# 1a.net
KiCad netlist of a schematic drawn in EAGLE
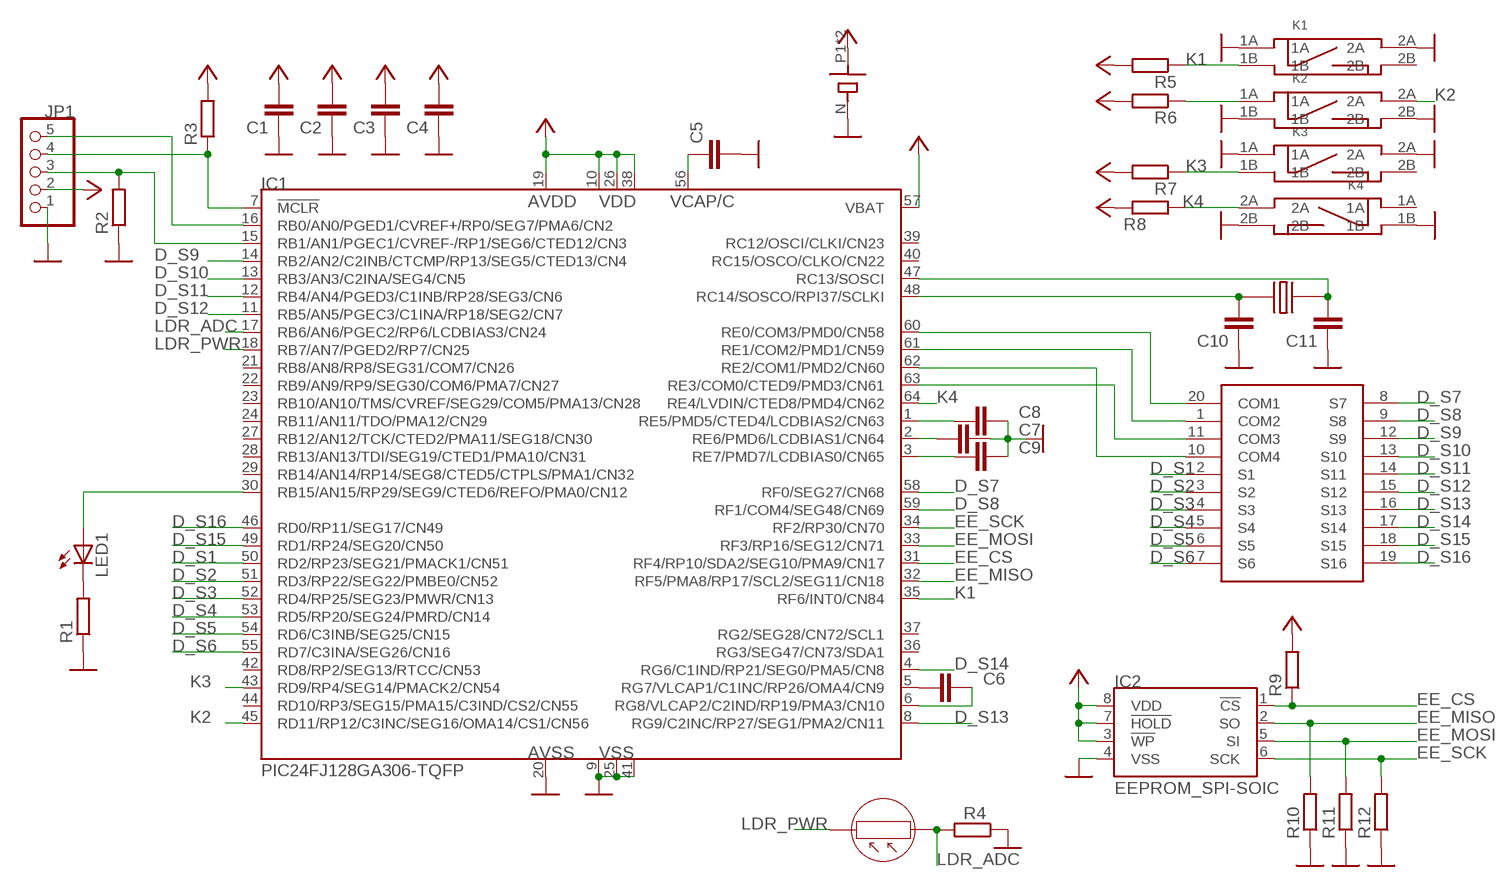
[diagram p0: schematic, sheet 1]

(export (version "E")
  (design (tool "Eeschema 10.0.6"))
  (components
    (comp (ref "C1")
      (value "C_1206")
      (footprint "eagle-import:R1206")
      (libsource (lib "eagle-import") (part "C_1206"))
    )
    (comp (ref "C2")
      (value "C_0603")
      (footprint "eagle-import:0603")
      (libsource (lib "eagle-import") (part "C_0603"))
    )
    (comp (ref "C3")
      (value "C_0603")
      (footprint "eagle-import:0603")
      (libsource (lib "eagle-import") (part "C_0603"))
    )
    (comp (ref "C4")
      (value "C_0603")
      (footprint "eagle-import:0603")
      (libsource (lib "eagle-import") (part "C_0603"))
    )
    (comp (ref "C5")
      (value "C_0603")
      (footprint "eagle-import:0603")
      (libsource (lib "eagle-import") (part "C_0603"))
    )
    (comp (ref "C6")
      (value "C_0603")
      (footprint "eagle-import:0603")
      (libsource (lib "eagle-import") (part "C_0603"))
    )
    (comp (ref "C7")
      (value "C_0603")
      (footprint "eagle-import:0603")
      (libsource (lib "eagle-import") (part "C_0603"))
    )
    (comp (ref "C8")
      (value "C_0603")
      (footprint "eagle-import:0603")
      (libsource (lib "eagle-import") (part "C_0603"))
    )
    (comp (ref "C9")
      (value "C_0603")
      (footprint "eagle-import:0603")
      (libsource (lib "eagle-import") (part "C_0603"))
    )
    (comp (ref "C10")
      (value "C_0603")
      (footprint "eagle-import:0603")
      (libsource (lib "eagle-import") (part "C_0603"))
    )
    (comp (ref "C11")
      (value "C_0603")
      (footprint "eagle-import:0603")
      (libsource (lib "eagle-import") (part "C_0603"))
    )
    (comp (ref "IC1")
      (value "PIC24FJ128GA306-TQFP")
      (footprint "eagle-import:TQFP64-10X10")
      (libsource (lib "eagle-import") (part "PIC24FJ128GA306-TQFP"))
    )
    (comp (ref "IC2")
      (value "EEPROM_SPI-SOIC")
      (footprint "eagle-import:SO-08")
      (libsource (lib "eagle-import") (part "EEPROM_SPI-SOIC"))
    )
    (comp (ref "JP1")
      (value "PINHD-1X05_2.00")
      (footprint "eagle-import:1X05M")
      (libsource (lib "eagle-import") (part "PINHD-1X05_2.00"))
    )
    (comp (ref "K1")
      (value "SWITCH_BD_B")
      (footprint "eagle-import:SW_SMD2")
      (libsource (lib "eagle-import") (part "SWITCH_BD_B"))
    )
    (comp (ref "K2")
      (value "SWITCH_BD_B")
      (footprint "eagle-import:SW_SMD2")
      (libsource (lib "eagle-import") (part "SWITCH_BD_B"))
    )
    (comp (ref "K3")
      (value "SWITCH_BD_B")
      (footprint "eagle-import:SW_SMD2")
      (libsource (lib "eagle-import") (part "SWITCH_BD_B"))
    )
    (comp (ref "K4")
      (value "SWITCH_BD_B")
      (footprint "eagle-import:SW_SMD2")
      (libsource (lib "eagle-import") (part "SWITCH_BD_B"))
    )
    (comp (ref "LCD1")
      (value "LCD_DE188")
      (footprint "eagle-import:LCD_DE188")
      (libsource (lib "eagle-import") (part "LCD_DE188"))
    )
    (comp (ref "LDR1")
      (value "LDR")
      (footprint "eagle-import:LDR_5")
      (libsource (lib "eagle-import") (part "LDR"))
    )
    (comp (ref "LED1")
      (value "LEDCHIPLED_0805")
      (footprint "eagle-import:CHIPLED_0805")
      (libsource (lib "eagle-import") (part "LEDCHIPLED_0805"))
    )
    (comp (ref "R1")
      (value "R_0603")
      (footprint "eagle-import:0603")
      (libsource (lib "eagle-import") (part "R_0603"))
    )
    (comp (ref "R2")
      (value "R_0603")
      (footprint "eagle-import:0603")
      (libsource (lib "eagle-import") (part "R_0603"))
    )
    (comp (ref "R3")
      (value "R_0603")
      (footprint "eagle-import:0603")
      (libsource (lib "eagle-import") (part "R_0603"))
    )
    (comp (ref "R4")
      (value "R_0603")
      (footprint "eagle-import:0603")
      (libsource (lib "eagle-import") (part "R_0603"))
    )
    (comp (ref "R5")
      (value "R_0603")
      (footprint "eagle-import:0603")
      (libsource (lib "eagle-import") (part "R_0603"))
    )
    (comp (ref "R6")
      (value "R_0603")
      (footprint "eagle-import:0603")
      (libsource (lib "eagle-import") (part "R_0603"))
    )
    (comp (ref "R7")
      (value "R_0603")
      (footprint "eagle-import:0603")
      (libsource (lib "eagle-import") (part "R_0603"))
    )
    (comp (ref "R8")
      (value "R_0603")
      (footprint "eagle-import:0603")
      (libsource (lib "eagle-import") (part "R_0603"))
    )
    (comp (ref "R9")
      (value "R_0603")
      (footprint "eagle-import:0603")
      (libsource (lib "eagle-import") (part "R_0603"))
    )
    (comp (ref "R10")
      (value "R_0603")
      (footprint "eagle-import:0603")
      (libsource (lib "eagle-import") (part "R_0603"))
    )
    (comp (ref "R11")
      (value "R_0603")
      (footprint "eagle-import:0603")
      (libsource (lib "eagle-import") (part "R_0603"))
    )
    (comp (ref "R12")
      (value "R_0603")
      (footprint "eagle-import:0603")
      (libsource (lib "eagle-import") (part "R_0603"))
    )
    (comp (ref "U$1")
      (value "BATTK3002")
      (footprint "eagle-import:BATT_KEYS3002")
      (libsource (lib "eagle-import") (part "BATTK3002"))
    )
    (comp (ref "X1")
      (value "CRYST_TC26MC146")
      (footprint "eagle-import:CRYST_MC146")
      (libsource (lib "eagle-import") (part "CRYST_TC26MC146"))
    )
  )
  (nets
    (net (code "1") (name "/D_S1") (class "Default")
      (node (ref "IC1") (pin "50") (pinfunction "RD2/RP23/SEG21/PMACK1/CN51_50") (pintype "bidirectional"))
      (node (ref "LCD1") (pin "2") (pinfunction "S1_2") (pintype "bidirectional"))
    )
    (net (code "2") (name "/D_S2") (class "Default")
      (node (ref "IC1") (pin "51") (pinfunction "RD3/RP22/SEG22/PMBE0/CN52_51") (pintype "bidirectional"))
      (node (ref "LCD1") (pin "3") (pinfunction "S2_3") (pintype "bidirectional"))
    )
    (net (code "3") (name "/D_S3") (class "Default")
      (node (ref "IC1") (pin "52") (pinfunction "RD4/RP25/SEG23/PMWR/CN13_52") (pintype "bidirectional"))
      (node (ref "LCD1") (pin "4") (pinfunction "S3_4") (pintype "bidirectional"))
    )
    (net (code "4") (name "/D_S4") (class "Default")
      (node (ref "IC1") (pin "53") (pinfunction "RD5/RP20/SEG24/PMRD/CN14_53") (pintype "bidirectional"))
      (node (ref "LCD1") (pin "5") (pinfunction "S4_5") (pintype "bidirectional"))
    )
    (net (code "5") (name "/D_S5") (class "Default")
      (node (ref "IC1") (pin "54") (pinfunction "RD6/C3INB/SEG25/CN15_54") (pintype "bidirectional"))
      (node (ref "LCD1") (pin "6") (pinfunction "S5_6") (pintype "bidirectional"))
    )
    (net (code "6") (name "/D_S6") (class "Default")
      (node (ref "IC1") (pin "55") (pinfunction "RD7/C3INA/SEG26/CN16_55") (pintype "bidirectional"))
      (node (ref "LCD1") (pin "7") (pinfunction "S6_7") (pintype "bidirectional"))
    )
    (net (code "7") (name "/D_S7") (class "Default")
      (node (ref "IC1") (pin "58") (pinfunction "RF0/SEG27/CN68_58") (pintype "bidirectional"))
      (node (ref "LCD1") (pin "8") (pinfunction "S7_8") (pintype "bidirectional"))
    )
    (net (code "8") (name "/D_S8") (class "Default")
      (node (ref "IC1") (pin "59") (pinfunction "RF1/COM4/SEG48/CN69_59") (pintype "bidirectional"))
      (node (ref "LCD1") (pin "9") (pinfunction "S8_9") (pintype "bidirectional"))
    )
    (net (code "9") (name "/D_S9") (class "Default")
      (node (ref "IC1") (pin "14") (pinfunction "RB2/AN2/C2INB/CTCMP/RP13/SEG5/CTED13/CN4_14") (pintype "bidirectional"))
      (node (ref "LCD1") (pin "12") (pinfunction "S9_12") (pintype "bidirectional"))
    )
    (net (code "10") (name "/D_S10") (class "Default")
      (node (ref "IC1") (pin "13") (pinfunction "RB3/AN3/C2INA/SEG4/CN5_13") (pintype "bidirectional"))
      (node (ref "LCD1") (pin "13") (pinfunction "S10_13") (pintype "bidirectional"))
    )
    (net (code "11") (name "/D_S11") (class "Default")
      (node (ref "IC1") (pin "12") (pinfunction "RB4/AN4/PGED3/C1INB/RP28/SEG3/CN6_12") (pintype "bidirectional"))
      (node (ref "LCD1") (pin "14") (pinfunction "S11_14") (pintype "bidirectional"))
    )
    (net (code "12") (name "/D_S12") (class "Default")
      (node (ref "IC1") (pin "11") (pinfunction "RB5/AN5/PGEC3/C1INA/RP18/SEG2/CN7_11") (pintype "bidirectional"))
      (node (ref "LCD1") (pin "15") (pinfunction "S12_15") (pintype "bidirectional"))
    )
    (net (code "13") (name "/D_S13") (class "Default")
      (node (ref "IC1") (pin "8") (pinfunction "RG9/C2INC/RP27/SEG1/PMA2/CN11_8") (pintype "bidirectional"))
      (node (ref "LCD1") (pin "16") (pinfunction "S13_16") (pintype "bidirectional"))
    )
    (net (code "14") (name "/D_S14") (class "Default")
      (node (ref "IC1") (pin "4") (pinfunction "RG6/C1IND/RP21/SEG0/PMA5/CN8_4") (pintype "bidirectional"))
      (node (ref "LCD1") (pin "17") (pinfunction "S14_17") (pintype "bidirectional"))
    )
    (net (code "15") (name "/D_S15") (class "Default")
      (node (ref "IC1") (pin "49") (pinfunction "RD1/RP24/SEG20/CN50_49") (pintype "bidirectional"))
      (node (ref "LCD1") (pin "18") (pinfunction "S15_18") (pintype "bidirectional"))
    )
    (net (code "16") (name "/D_S16") (class "Default")
      (node (ref "IC1") (pin "46") (pinfunction "RD0/RP11/SEG17/CN49_46") (pintype "bidirectional"))
      (node (ref "LCD1") (pin "19") (pinfunction "S16_19") (pintype "bidirectional"))
    )
    (net (code "17") (name "/EE_CS") (class "Default")
      (node (ref "IC1") (pin "31") (pinfunction "RF4/RP10/SDA2/SEG10/PMA9/CN17_31") (pintype "bidirectional"))
      (node (ref "IC2") (pin "1") (pinfunction "~{CS}_1") (pintype "input"))
      (node (ref "R9") (pin "1") (pinfunction "1_1") (pintype "passive"))
    )
    (net (code "18") (name "/EE_MISO") (class "Default")
      (node (ref "IC1") (pin "32") (pinfunction "RF5/PMA8/RP17/SCL2/SEG11/CN18_32") (pintype "bidirectional"))
      (node (ref "IC2") (pin "2") (pinfunction "SO_2") (pintype "input"))
      (node (ref "R10") (pin "2") (pinfunction "2_2") (pintype "passive"))
    )
    (net (code "19") (name "/EE_MOSI") (class "Default")
      (node (ref "IC1") (pin "33") (pinfunction "RF3/RP16/SEG12/CN71_33") (pintype "bidirectional"))
      (node (ref "IC2") (pin "5") (pinfunction "SI_5") (pintype "input"))
      (node (ref "R11") (pin "2") (pinfunction "2_2") (pintype "passive"))
    )
    (net (code "20") (name "/EE_SCK") (class "Default")
      (node (ref "IC1") (pin "34") (pinfunction "RF2/RP30/CN70_34") (pintype "bidirectional"))
      (node (ref "IC2") (pin "6") (pinfunction "SCK_6") (pintype "input"))
      (node (ref "R12") (pin "2") (pinfunction "2_2") (pintype "passive"))
    )
    (net (code "21") (name "/K1") (class "Default")
      (node (ref "IC1") (pin "35") (pinfunction "RF6/INT0/CN84_35") (pintype "bidirectional"))
      (node (ref "K1") (pin "1B") (pinfunction "1B_1B") (pintype "bidirectional"))
      (node (ref "R5") (pin "1") (pinfunction "1_1") (pintype "passive"))
    )
    (net (code "22") (name "/K2") (class "Default")
      (node (ref "IC1") (pin "45") (pinfunction "RD11/RP12/C3INC/SEG16/OMA14/CS1/CN56_45") (pintype "bidirectional"))
      (node (ref "K2") (pin "2A") (pinfunction "2A_2A") (pintype "bidirectional"))
    )
    (net (code "23") (name "/K3") (class "Default")
      (node (ref "IC1") (pin "43") (pinfunction "RD9/RP4/SEG14/PMACK2/CN54_43") (pintype "bidirectional"))
      (node (ref "K3") (pin "1B") (pinfunction "1B_1B") (pintype "bidirectional"))
      (node (ref "R7") (pin "1") (pinfunction "1_1") (pintype "passive"))
    )
    (net (code "24") (name "/K4") (class "Default")
      (node (ref "IC1") (pin "64") (pinfunction "RE4/LVDIN/CTED8/PMD4/CN62_64") (pintype "bidirectional"))
      (node (ref "K4") (pin "2A") (pinfunction "2A_2A") (pintype "bidirectional"))
      (node (ref "R8") (pin "2") (pinfunction "2_2") (pintype "passive"))
    )
    (net (code "25") (name "/LDR_ADC") (class "Default")
      (node (ref "IC1") (pin "17") (pinfunction "RB6/AN6/PGEC2/RP6/LCDBIAS3/CN24_17") (pintype "bidirectional"))
      (node (ref "LDR1") (pin "P$1") (pinfunction "P$1_P$1") (pintype "bidirectional"))
      (node (ref "R4") (pin "2") (pinfunction "2_2") (pintype "passive"))
    )
    (net (code "26") (name "/LDR_PWR") (class "Default")
      (node (ref "IC1") (pin "18") (pinfunction "RB7/AN7/PGED2/RP7/CN25_18") (pintype "bidirectional"))
      (node (ref "LDR1") (pin "P$2") (pinfunction "P$2_P$2") (pintype "bidirectional"))
    )
    (net (code "27") (name "GND") (class "Default")
      (node (ref "C1") (pin "1") (pinfunction "1_1") (pintype "passive"))
      (node (ref "C10") (pin "1") (pinfunction "1_1") (pintype "passive"))
      (node (ref "C11") (pin "1") (pinfunction "1_1") (pintype "passive"))
      (node (ref "C2") (pin "1") (pinfunction "1_1") (pintype "passive"))
      (node (ref "C3") (pin "1") (pinfunction "1_1") (pintype "passive"))
      (node (ref "C4") (pin "1") (pinfunction "1_1") (pintype "passive"))
      (node (ref "C5") (pin "2") (pinfunction "2_2") (pintype "passive"))
      (node (ref "C7") (pin "1") (pinfunction "1_1") (pintype "passive"))
      (node (ref "C8") (pin "1") (pinfunction "1_1") (pintype "passive"))
      (node (ref "C9") (pin "1") (pinfunction "1_1") (pintype "passive"))
      (node (ref "IC1") (pin "20") (pinfunction "AVSS_20") (pintype "power_in"))
      (node (ref "IC1") (pin "25") (pinfunction "VSS_25") (pintype "power_in"))
      (node (ref "IC1") (pin "41") (pinfunction "VSS_41") (pintype "power_in"))
      (node (ref "IC1") (pin "9") (pinfunction "VSS_9") (pintype "power_in"))
      (node (ref "IC2") (pin "4") (pinfunction "VSS_4") (pintype "power_in"))
      (node (ref "JP1") (pin "1") (pinfunction "1_1") (pintype "passive"))
      (node (ref "K1") (pin "1A") (pinfunction "1A_1A") (pintype "bidirectional"))
      (node (ref "K1") (pin "2A") (pinfunction "2A_2A") (pintype "bidirectional"))
      (node (ref "K2") (pin "1B") (pinfunction "1B_1B") (pintype "bidirectional"))
      (node (ref "K2") (pin "2B") (pinfunction "2B_2B") (pintype "bidirectional"))
      (node (ref "K3") (pin "1A") (pinfunction "1A_1A") (pintype "bidirectional"))
      (node (ref "K3") (pin "2A") (pinfunction "2A_2A") (pintype "bidirectional"))
      (node (ref "K4") (pin "1B") (pinfunction "1B_1B") (pintype "bidirectional"))
      (node (ref "K4") (pin "2B") (pinfunction "2B_2B") (pintype "bidirectional"))
      (node (ref "R1") (pin "1") (pinfunction "1_1") (pintype "passive"))
      (node (ref "R10") (pin "1") (pinfunction "1_1") (pintype "passive"))
      (node (ref "R11") (pin "1") (pinfunction "1_1") (pintype "passive"))
      (node (ref "R12") (pin "1") (pinfunction "1_1") (pintype "passive"))
      (node (ref "R2") (pin "1") (pinfunction "1_1") (pintype "passive"))
      (node (ref "R4") (pin "1") (pinfunction "1_1") (pintype "passive"))
      (node (ref "U$1") (pin "N") (pinfunction "M_N") (pintype "bidirectional"))
    )
    (net (code "28") (name "Net-(IC1-C)") (class "Default")
      (node (ref "C5") (pin "1") (pinfunction "1_1") (pintype "passive"))
      (node (ref "IC1") (pin "56") (pinfunction "C_56") (pintype "power_in"))
    )
    (net (code "29") (name "Net-(IC1-RB0{slash}AN0{slash}PGED1{slash}CVREF+{slash}RP0{slash}SEG7{slash}PMA6{slash}CN2)") (class "Default")
      (node (ref "IC1") (pin "16") (pinfunction "RB0/AN0/PGED1/CVREF+/RP0/SEG7/PMA6/CN2_16") (pintype "bidirectional"))
      (node (ref "JP1") (pin "5") (pinfunction "5_5") (pintype "passive"))
    )
    (net (code "30") (name "Net-(IC1-RB1{slash}AN1{slash}PGEC1{slash}CVREF-{slash}RP1{slash}SEG6{slash}CTED12{slash}CN3)") (class "Default")
      (node (ref "IC1") (pin "15") (pinfunction "RB1/AN1/PGEC1/CVREF-/RP1/SEG6/CTED12/CN3_15") (pintype "bidirectional"))
      (node (ref "JP1") (pin "3") (pinfunction "3_3") (pintype "passive"))
      (node (ref "R2") (pin "2") (pinfunction "2_2") (pintype "passive"))
    )
    (net (code "31") (name "Net-(IC1-RB15{slash}AN15{slash}RP29{slash}SEG9{slash}CTED6{slash}REFO{slash}PMA0{slash}CN12)") (class "Default")
      (node (ref "IC1") (pin "30") (pinfunction "RB15/AN15/RP29/SEG9/CTED6/REFO/PMA0/CN12_30") (pintype "bidirectional"))
      (node (ref "LED1") (pin "A") (pinfunction "A_A") (pintype "passive"))
    )
    (net (code "32") (name "Net-(IC1-RC13{slash}SOSCI)") (class "Default")
      (node (ref "C11") (pin "2") (pinfunction "2_2") (pintype "passive"))
      (node (ref "IC1") (pin "47") (pinfunction "RC13/SOSCI_47") (pintype "bidirectional"))
      (node (ref "X1") (pin "1") (pinfunction "P$1_1") (pintype "bidirectional"))
    )
    (net (code "33") (name "Net-(IC1-RC14{slash}SOSCO{slash}RPI37{slash}SCLKI)") (class "Default")
      (node (ref "C10") (pin "2") (pinfunction "2_2") (pintype "passive"))
      (node (ref "IC1") (pin "48") (pinfunction "RC14/SOSCO/RPI37/SCLKI_48") (pintype "bidirectional"))
      (node (ref "X1") (pin "4") (pinfunction "P$2_4") (pintype "bidirectional"))
    )
    (net (code "34") (name "Net-(IC1-RE0{slash}COM3{slash}PMD0{slash}CN58)") (class "Default")
      (node (ref "IC1") (pin "60") (pinfunction "RE0/COM3/PMD0/CN58_60") (pintype "bidirectional"))
      (node (ref "LCD1") (pin "20") (pinfunction "COM1_20") (pintype "bidirectional"))
    )
    (net (code "35") (name "Net-(IC1-RE1{slash}COM2{slash}PMD1{slash}CN59)") (class "Default")
      (node (ref "IC1") (pin "61") (pinfunction "RE1/COM2/PMD1/CN59_61") (pintype "bidirectional"))
      (node (ref "LCD1") (pin "1") (pinfunction "COM2_1") (pintype "bidirectional"))
    )
    (net (code "36") (name "Net-(IC1-RE2{slash}COM1{slash}PMD2{slash}CN60)") (class "Default")
      (node (ref "IC1") (pin "62") (pinfunction "RE2/COM1/PMD2/CN60_62") (pintype "bidirectional"))
      (node (ref "LCD1") (pin "10") (pinfunction "COM4_10") (pintype "bidirectional"))
    )
    (net (code "37") (name "Net-(IC1-RE3{slash}COM0{slash}CTED9{slash}PMD3{slash}CN61)") (class "Default")
      (node (ref "IC1") (pin "63") (pinfunction "RE3/COM0/CTED9/PMD3/CN61_63") (pintype "bidirectional"))
      (node (ref "LCD1") (pin "11") (pinfunction "COM3_11") (pintype "bidirectional"))
    )
    (net (code "38") (name "Net-(IC1-RE5{slash}PMD5{slash}CTED4{slash}LCDBIAS2{slash}CN63)") (class "Default")
      (node (ref "C8") (pin "2") (pinfunction "2_2") (pintype "passive"))
      (node (ref "IC1") (pin "1") (pinfunction "RE5/PMD5/CTED4/LCDBIAS2/CN63_1") (pintype "bidirectional"))
    )
    (net (code "39") (name "Net-(IC1-RE6{slash}PMD6{slash}LCDBIAS1{slash}CN64)") (class "Default")
      (node (ref "C7") (pin "2") (pinfunction "2_2") (pintype "passive"))
      (node (ref "IC1") (pin "2") (pinfunction "RE6/PMD6/LCDBIAS1/CN64_2") (pintype "bidirectional"))
    )
    (net (code "40") (name "Net-(IC1-RE7{slash}PMD7{slash}LCDBIAS0{slash}CN65)") (class "Default")
      (node (ref "C9") (pin "2") (pinfunction "2_2") (pintype "passive"))
      (node (ref "IC1") (pin "3") (pinfunction "RE7/PMD7/LCDBIAS0/CN65_3") (pintype "bidirectional"))
    )
    (net (code "41") (name "Net-(IC1-RG7{slash}VLCAP1{slash}C1INC{slash}RP26{slash}OMA4{slash}CN9)") (class "Default")
      (node (ref "C6") (pin "2") (pinfunction "2_2") (pintype "passive"))
      (node (ref "IC1") (pin "5") (pinfunction "RG7/VLCAP1/C1INC/RP26/OMA4/CN9_5") (pintype "bidirectional"))
    )
    (net (code "42") (name "Net-(IC1-RG8{slash}VLCAP2{slash}C2IND{slash}RP19{slash}PMA3{slash}CN10)") (class "Default")
      (node (ref "C6") (pin "1") (pinfunction "1_1") (pintype "passive"))
      (node (ref "IC1") (pin "6") (pinfunction "RG8/VLCAP2/C2IND/RP19/PMA3/CN10_6") (pintype "bidirectional"))
    )
    (net (code "43") (name "Net-(IC1-~{MCLR})") (class "Default")
      (node (ref "IC1") (pin "7") (pinfunction "~{MCLR}_7") (pintype "bidirectional"))
      (node (ref "JP1") (pin "4") (pinfunction "4_4") (pintype "passive"))
      (node (ref "R3") (pin "1") (pinfunction "1_1") (pintype "passive"))
    )
    (net (code "44") (name "Net-(K2-Pad1A)") (class "Default")
      (node (ref "K2") (pin "1A") (pinfunction "1A_1A") (pintype "bidirectional"))
      (node (ref "R6") (pin "1") (pinfunction "1_1") (pintype "passive"))
    )
    (net (code "45") (name "Net-(LED1-PadC)") (class "Default")
      (node (ref "LED1") (pin "C") (pinfunction "C_C") (pintype "passive"))
      (node (ref "R1") (pin "2") (pinfunction "2_2") (pintype "passive"))
    )
    (net (code "46") (name "VCC") (class "Default")
      (node (ref "C1") (pin "2") (pinfunction "2_2") (pintype "passive"))
      (node (ref "C2") (pin "2") (pinfunction "2_2") (pintype "passive"))
      (node (ref "C3") (pin "2") (pinfunction "2_2") (pintype "passive"))
      (node (ref "C4") (pin "2") (pinfunction "2_2") (pintype "passive"))
      (node (ref "IC1") (pin "10") (pinfunction "VDD_10") (pintype "power_in"))
      (node (ref "IC1") (pin "19") (pinfunction "AVDD_19") (pintype "power_in"))
      (node (ref "IC1") (pin "26") (pinfunction "VDD_26") (pintype "power_in"))
      (node (ref "IC1") (pin "38") (pinfunction "VDD_38") (pintype "power_in"))
      (node (ref "IC1") (pin "57") (pinfunction "VBAT_57") (pintype "power_in"))
      (node (ref "IC2") (pin "3") (pinfunction "~{WP}_3") (pintype "input"))
      (node (ref "IC2") (pin "7") (pinfunction "~{HOLD}_7") (pintype "input"))
      (node (ref "IC2") (pin "8") (pinfunction "VDD_8") (pintype "power_in"))
      (node (ref "JP1") (pin "2") (pinfunction "2_2") (pintype "passive"))
      (node (ref "R3") (pin "2") (pinfunction "2_2") (pintype "passive"))
      (node (ref "R5") (pin "2") (pinfunction "2_2") (pintype "passive"))
      (node (ref "R6") (pin "2") (pinfunction "2_2") (pintype "passive"))
      (node (ref "R7") (pin "2") (pinfunction "2_2") (pintype "passive"))
      (node (ref "R8") (pin "1") (pinfunction "1_1") (pintype "passive"))
      (node (ref "R9") (pin "2") (pinfunction "2_2") (pintype "passive"))
      (node (ref "U$1") (pin "P1") (pinfunction "P_P1") (pintype "bidirectional"))
      (node (ref "U$1") (pin "P2") (pinfunction "P_P2") (pintype "bidirectional"))
    )
    (net (code "47") (name "unconnected-(IC1-RB8{slash}AN8{slash}RP8{slash}SEG31{slash}COM7{slash}CN26-Pad21)") (class "Default")
      (node (ref "IC1") (pin "21") (pinfunction "RB8/AN8/RP8/SEG31/COM7/CN26_21") (pintype "bidirectional"))
    )
    (net (code "48") (name "unconnected-(IC1-RB9{slash}AN9{slash}RP9{slash}SEG30{slash}COM6{slash}PMA7{slash}CN27-Pad22)") (class "Default")
      (node (ref "IC1") (pin "22") (pinfunction "RB9/AN9/RP9/SEG30/COM6/PMA7/CN27_22") (pintype "bidirectional"))
    )
    (net (code "49") (name "unconnected-(IC1-RB10{slash}AN10{slash}TMS{slash}CVREF{slash}SEG29{slash}COM5{slash}PMA13{slash}CN28-Pad23)") (class "Default")
      (node (ref "IC1") (pin "23") (pinfunction "RB10/AN10/TMS/CVREF/SEG29/COM5/PMA13/CN28_23") (pintype "bidirectional"))
    )
    (net (code "50") (name "unconnected-(IC1-RB11{slash}AN11{slash}TDO{slash}PMA12{slash}CN29-Pad24)") (class "Default")
      (node (ref "IC1") (pin "24") (pinfunction "RB11/AN11/TDO/PMA12/CN29_24") (pintype "bidirectional"))
    )
    (net (code "51") (name "unconnected-(IC1-RB12{slash}AN12{slash}TCK{slash}CTED2{slash}PMA11{slash}SEG18{slash}CN30-Pad27)") (class "Default")
      (node (ref "IC1") (pin "27") (pinfunction "RB12/AN12/TCK/CTED2/PMA11/SEG18/CN30_27") (pintype "bidirectional"))
    )
    (net (code "52") (name "unconnected-(IC1-RB13{slash}AN13{slash}TDI{slash}SEG19{slash}CTED1{slash}PMA10{slash}CN31-Pad28)") (class "Default")
      (node (ref "IC1") (pin "28") (pinfunction "RB13/AN13/TDI/SEG19/CTED1/PMA10/CN31_28") (pintype "bidirectional"))
    )
    (net (code "53") (name "unconnected-(IC1-RB14{slash}AN14{slash}RP14{slash}SEG8{slash}CTED5{slash}CTPLS{slash}PMA1{slash}CN32-Pad29)") (class "Default")
      (node (ref "IC1") (pin "29") (pinfunction "RB14/AN14/RP14/SEG8/CTED5/CTPLS/PMA1/CN32_29") (pintype "bidirectional"))
    )
    (net (code "54") (name "unconnected-(IC1-RC12{slash}OSCI{slash}CLKI{slash}CN23-Pad39)") (class "Default")
      (node (ref "IC1") (pin "39") (pinfunction "RC12/OSCI/CLKI/CN23_39") (pintype "bidirectional"))
    )
    (net (code "55") (name "unconnected-(IC1-RC15{slash}OSCO{slash}CLKO{slash}CN22-Pad40)") (class "Default")
      (node (ref "IC1") (pin "40") (pinfunction "RC15/OSCO/CLKO/CN22_40") (pintype "bidirectional"))
    )
    (net (code "56") (name "unconnected-(IC1-RD8{slash}RP2{slash}SEG13{slash}RTCC{slash}CN53-Pad42)") (class "Default")
      (node (ref "IC1") (pin "42") (pinfunction "RD8/RP2/SEG13/RTCC/CN53_42") (pintype "bidirectional"))
    )
    (net (code "57") (name "unconnected-(IC1-RD10{slash}RP3{slash}SEG15{slash}PMA15{slash}C3IND{slash}CS2{slash}CN55-Pad44)") (class "Default")
      (node (ref "IC1") (pin "44") (pinfunction "RD10/RP3/SEG15/PMA15/C3IND/CS2/CN55_44") (pintype "bidirectional"))
    )
    (net (code "58") (name "unconnected-(IC1-RG2{slash}SEG28{slash}CN72{slash}SCL1-Pad37)") (class "Default")
      (node (ref "IC1") (pin "37") (pinfunction "RG2/SEG28/CN72/SCL1_37") (pintype "bidirectional"))
    )
    (net (code "59") (name "unconnected-(IC1-RG3{slash}SEG47{slash}CN73{slash}SDA1-Pad36)") (class "Default")
      (node (ref "IC1") (pin "36") (pinfunction "RG3/SEG47/CN73/SDA1_36") (pintype "bidirectional"))
    )
    (net (code "60") (name "unconnected-(K1-Pad2B)") (class "Default")
      (node (ref "K1") (pin "2B") (pinfunction "2B_2B") (pintype "bidirectional"))
    )
    (net (code "61") (name "unconnected-(K3-Pad2B)") (class "Default")
      (node (ref "K3") (pin "2B") (pinfunction "2B_2B") (pintype "bidirectional"))
    )
    (net (code "62") (name "unconnected-(K4-Pad1A)") (class "Default")
      (node (ref "K4") (pin "1A") (pinfunction "1A_1A") (pintype "bidirectional"))
    )
  )
)
